# HandschuhSimplified.net
KiCad netlist of a schematic drawn in EAGLE
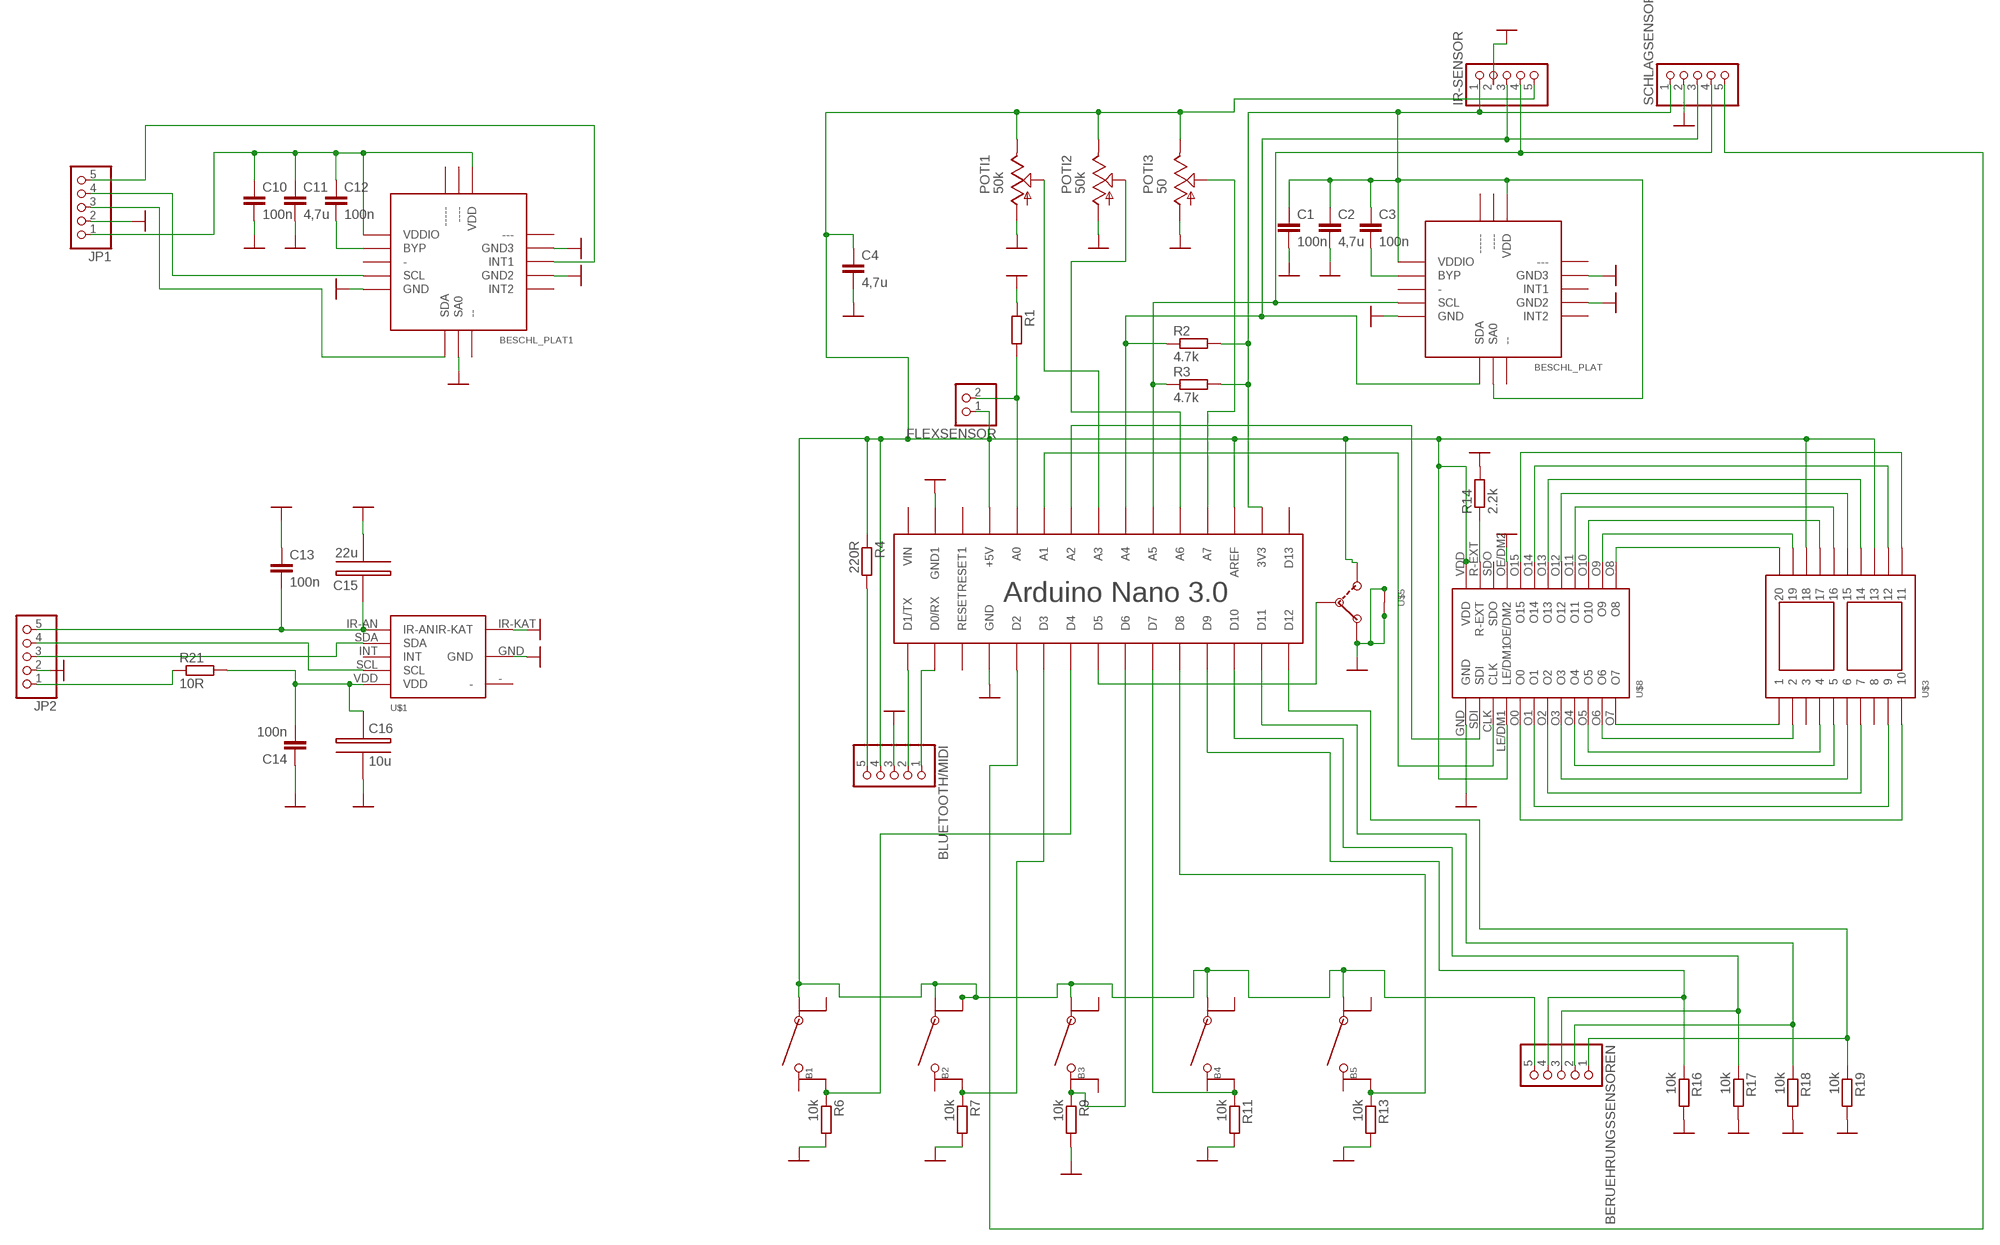
[diagram p0: schematic, sheet 1]

(export (version "E")
  (design (tool "Eeschema 10.0.6"))
  (components
    (comp (ref "B1")
      (value "BUTTON")
      (footprint "eagle-import:BUTTON")
      (libsource (lib "eagle-import") (part "BUTTON"))
    )
    (comp (ref "B2")
      (value "BUTTON")
      (footprint "eagle-import:BUTTON")
      (libsource (lib "eagle-import") (part "BUTTON"))
    )
    (comp (ref "B3")
      (value "BUTTON")
      (footprint "eagle-import:BUTTON")
      (libsource (lib "eagle-import") (part "BUTTON"))
    )
    (comp (ref "B4")
      (value "BUTTON")
      (footprint "eagle-import:BUTTON")
      (libsource (lib "eagle-import") (part "BUTTON"))
    )
    (comp (ref "B5")
      (value "BUTTON")
      (footprint "eagle-import:BUTTON")
      (libsource (lib "eagle-import") (part "BUTTON"))
    )
    (comp (ref "BERUEHRUNGSSENSOREN")
      (value "PINHD-1X5/90")
      (footprint "eagle-import:1X05_90")
      (libsource (lib "eagle-import") (part "PINHD-1X5/90"))
    )
    (comp (ref "BESCHL_PLAT")
      (value "BESCHLEUNIGSUNGSSENSOR")
      (footprint "eagle-import:BESCHLEUNIGUNGSSENSOR")
      (libsource (lib "eagle-import") (part "BESCHLEUNIGSUNGSSENSOR"))
    )
    (comp (ref "BESCHL_PLAT1")
      (value "BESCHLEUNIGSUNGSSENSOR")
      (footprint "eagle-import:BESCHLEUNIGUNGSSENSOR")
      (libsource (lib "eagle-import") (part "BESCHLEUNIGSUNGSSENSOR"))
    )
    (comp (ref "BLUETOOTH/MIDI")
      (value "PINHD-1X5/90")
      (footprint "eagle-import:1X05_90")
      (libsource (lib "eagle-import") (part "PINHD-1X5/90"))
    )
    (comp (ref "C1")
      (value "100n")
      (footprint "eagle-import:C0805")
      (libsource (lib "eagle-import") (part "C-EUC0805"))
    )
    (comp (ref "C2")
      (value "4,7u")
      (footprint "eagle-import:C0805")
      (libsource (lib "eagle-import") (part "C-EUC0805"))
    )
    (comp (ref "C3")
      (value "100n")
      (footprint "eagle-import:C0805")
      (libsource (lib "eagle-import") (part "C-EUC0805"))
    )
    (comp (ref "C4")
      (value "4,7u")
      (footprint "eagle-import:C0805")
      (libsource (lib "eagle-import") (part "C-EUC0805"))
    )
    (comp (ref "C10")
      (value "100n")
      (footprint "eagle-import:C0805")
      (libsource (lib "eagle-import") (part "C-EUC0805"))
    )
    (comp (ref "C11")
      (value "4,7u")
      (footprint "eagle-import:C0805")
      (libsource (lib "eagle-import") (part "C-EUC0805"))
    )
    (comp (ref "C12")
      (value "100n")
      (footprint "eagle-import:C0805")
      (libsource (lib "eagle-import") (part "C-EUC0805"))
    )
    (comp (ref "C13")
      (value "100n")
      (footprint "eagle-import:C0805")
      (libsource (lib "eagle-import") (part "C-EUC0805"))
    )
    (comp (ref "C14")
      (value "100n")
      (footprint "eagle-import:C0805")
      (libsource (lib "eagle-import") (part "C-EUC0805"))
    )
    (comp (ref "C15")
      (value "22u")
      (footprint "eagle-import:22U-KONDENSATOR")
      (libsource (lib "eagle-import") (part "22U-KONDENSATOR"))
    )
    (comp (ref "C16")
      (value "10u")
      (footprint "eagle-import:22U-KONDENSATOR")
      (libsource (lib "eagle-import") (part "22U-KONDENSATOR"))
    )
    (comp (ref "FLEXSENSOR")
      (value "PINHD-1X2/90")
      (footprint "eagle-import:1X02_90")
      (libsource (lib "eagle-import") (part "PINHD-1X2/90"))
    )
    (comp (ref "IR-SENSOR")
      (value "PINHD-1X5/90")
      (footprint "eagle-import:1X05_90")
      (libsource (lib "eagle-import") (part "PINHD-1X5/90"))
    )
    (comp (ref "JP1")
      (value "PINHD-1X5/90")
      (footprint "eagle-import:1X05_90")
      (libsource (lib "eagle-import") (part "PINHD-1X5/90"))
    )
    (comp (ref "JP2")
      (value "PINHD-1X5/90")
      (footprint "eagle-import:1X05_90")
      (libsource (lib "eagle-import") (part "PINHD-1X5/90"))
    )
    (comp (ref "POTI1")
      (value "50k")
      (footprint "eagle-import:POTI")
      (libsource (lib "eagle-import") (part "POTI"))
    )
    (comp (ref "POTI2")
      (value "50k")
      (footprint "eagle-import:POTI")
      (libsource (lib "eagle-import") (part "POTI"))
    )
    (comp (ref "POTI3")
      (value "50")
      (footprint "eagle-import:POTI")
      (libsource (lib "eagle-import") (part "POTI"))
    )
    (comp (ref "R1")
      (value "R-EU_M0805")
      (footprint "eagle-import:M0805")
      (libsource (lib "eagle-import") (part "R-EU_M0805"))
    )
    (comp (ref "R2")
      (value "4.7k")
      (footprint "eagle-import:M0805")
      (libsource (lib "eagle-import") (part "R-EU_M0805"))
    )
    (comp (ref "R3")
      (value "4.7k")
      (footprint "eagle-import:M0805")
      (libsource (lib "eagle-import") (part "R-EU_M0805"))
    )
    (comp (ref "R4")
      (value "220R")
      (footprint "eagle-import:M0805")
      (libsource (lib "eagle-import") (part "R-EU_M0805"))
    )
    (comp (ref "R6")
      (value "10k")
      (footprint "eagle-import:M0805")
      (libsource (lib "eagle-import") (part "R-EU_M0805"))
    )
    (comp (ref "R7")
      (value "10k")
      (footprint "eagle-import:M0805")
      (libsource (lib "eagle-import") (part "R-EU_M0805"))
    )
    (comp (ref "R9")
      (value "10k")
      (footprint "eagle-import:M0805")
      (libsource (lib "eagle-import") (part "R-EU_M0805"))
    )
    (comp (ref "R11")
      (value "10k")
      (footprint "eagle-import:M0805")
      (libsource (lib "eagle-import") (part "R-EU_M0805"))
    )
    (comp (ref "R13")
      (value "10k")
      (footprint "eagle-import:M0805")
      (libsource (lib "eagle-import") (part "R-EU_M0805"))
    )
    (comp (ref "R14")
      (value "2.2k")
      (footprint "eagle-import:M0805")
      (libsource (lib "eagle-import") (part "R-EU_M0805"))
    )
    (comp (ref "R16")
      (value "10k")
      (footprint "eagle-import:M0805")
      (libsource (lib "eagle-import") (part "R-EU_M0805"))
    )
    (comp (ref "R17")
      (value "10k")
      (footprint "eagle-import:M0805")
      (libsource (lib "eagle-import") (part "R-EU_M0805"))
    )
    (comp (ref "R18")
      (value "10k")
      (footprint "eagle-import:M0805")
      (libsource (lib "eagle-import") (part "R-EU_M0805"))
    )
    (comp (ref "R19")
      (value "10k")
      (footprint "eagle-import:M0805")
      (libsource (lib "eagle-import") (part "R-EU_M0805"))
    )
    (comp (ref "R21")
      (value "10R")
      (footprint "eagle-import:M0805")
      (libsource (lib "eagle-import") (part "R-EU_M0805"))
    )
    (comp (ref "SCHLAGSENSOR")
      (value "PINHD-1X5/90")
      (footprint "eagle-import:1X05_90")
      (libsource (lib "eagle-import") (part "PINHD-1X5/90"))
    )
    (comp (ref "U$1")
      (value "IR-SENSOR")
      (footprint "eagle-import:IR-SENSOR")
      (libsource (lib "eagle-import") (part "IR-SENSOR"))
    )
    (comp (ref "U$2")
      (value "ARDUINONANO")
      (footprint "eagle-import:PDIP-32")
      (libsource (lib "eagle-import") (part "ARDUINONANO"))
    )
    (comp (ref "U$3")
      (value "7-SEGMENT")
      (footprint "eagle-import:7-SEGMENT")
      (libsource (lib "eagle-import") (part "7-SEGMENT"))
    )
    (comp (ref "U$5")
      (value "SCHALTER")
      (footprint "eagle-import:SCHALTER")
      (libsource (lib "eagle-import") (part "SCHALTER"))
    )
    (comp (ref "U$8")
      (value "7-SEGMENT-TREIBER")
      (footprint "eagle-import:7-SEGMENT-TREIBER")
      (libsource (lib "eagle-import") (part "7-SEGMENT-TREIBER"))
    )
  )
  (nets
    (net (code "1") (name "Net-(B1-Pad2)") (class "Default")
      (node (ref "B1") (pin "2") (pinfunction "2_2") (pintype "bidirectional"))
      (node (ref "R6") (pin "1") (pinfunction "1_1") (pintype "passive"))
      (node (ref "U$2") (pin "D4") (pinfunction "D4_D4") (pintype "bidirectional"))
    )
    (net (code "2") (name "Net-(B1-Pad3)") (class "Default")
      (node (ref "B1") (pin "3") (pinfunction "3_3") (pintype "bidirectional"))
      (node (ref "B2") (pin "3") (pinfunction "3_3") (pintype "bidirectional"))
      (node (ref "B2") (pin "4") (pinfunction "4_4") (pintype "bidirectional"))
      (node (ref "B3") (pin "3") (pinfunction "3_3") (pintype "bidirectional"))
      (node (ref "B4") (pin "3") (pinfunction "3_3") (pintype "bidirectional"))
      (node (ref "B5") (pin "3") (pinfunction "3_3") (pintype "bidirectional"))
      (node (ref "BERUEHRUNGSSENSOREN") (pin "5") (pinfunction "5_5") (pintype "passive"))
      (node (ref "BLUETOOTH/MIDI") (pin "4") (pinfunction "4_4") (pintype "passive"))
      (node (ref "C4") (pin "1") (pinfunction "1_1") (pintype "passive"))
      (node (ref "FLEXSENSOR") (pin "1") (pinfunction "1_1") (pintype "passive"))
      (node (ref "IR-SENSOR") (pin "5") (pinfunction "5_5") (pintype "passive"))
      (node (ref "POTI1") (pin "VCC") (pinfunction "VCC_VCC") (pintype "passive"))
      (node (ref "POTI2") (pin "VCC") (pinfunction "VCC_VCC") (pintype "passive"))
      (node (ref "POTI3") (pin "VCC") (pinfunction "VCC_VCC") (pintype "passive"))
      (node (ref "R4") (pin "1") (pinfunction "1_1") (pintype "passive"))
      (node (ref "U$2") (pin "+5V") (pinfunction "+5V_+5V") (pintype "bidirectional"))
      (node (ref "U$2") (pin "AREF") (pinfunction "AREF_AREF") (pintype "bidirectional"))
      (node (ref "U$3") (pin "13") (pinfunction "13_13") (pintype "bidirectional"))
      (node (ref "U$3") (pin "18") (pinfunction "18_18") (pintype "bidirectional"))
      (node (ref "U$5") (pin "3") (pinfunction "3_3") (pintype "bidirectional"))
      (node (ref "U$8") (pin "LE/DM1") (pinfunction "LE/DM1_LE/DM1") (pintype "bidirectional"))
      (node (ref "U$8") (pin "VDD") (pinfunction "VDD_VDD") (pintype "bidirectional"))
    )
    (net (code "3") (name "Net-(B2-Pad2)") (class "Default")
      (node (ref "B2") (pin "2") (pinfunction "2_2") (pintype "bidirectional"))
      (node (ref "R7") (pin "1") (pinfunction "1_1") (pintype "passive"))
      (node (ref "U$2") (pin "D3") (pinfunction "D3_D3") (pintype "bidirectional"))
    )
    (net (code "4") (name "Net-(B3-Pad1)") (class "Default")
      (node (ref "B3") (pin "1") (pinfunction "1_1") (pintype "bidirectional"))
      (node (ref "R9") (pin "1") (pinfunction "1_1") (pintype "passive"))
      (node (ref "U$2") (pin "D6") (pinfunction "D6_D6") (pintype "bidirectional"))
    )
    (net (code "5") (name "Net-(B4-Pad2)") (class "Default")
      (node (ref "B4") (pin "2") (pinfunction "2_2") (pintype "bidirectional"))
      (node (ref "R11") (pin "1") (pinfunction "1_1") (pintype "passive"))
      (node (ref "U$2") (pin "D7") (pinfunction "D7_D7") (pintype "bidirectional"))
    )
    (net (code "6") (name "Net-(B5-Pad2)") (class "Default")
      (node (ref "B5") (pin "2") (pinfunction "2_2") (pintype "bidirectional"))
      (node (ref "R13") (pin "1") (pinfunction "1_1") (pintype "passive"))
      (node (ref "U$2") (pin "D8") (pinfunction "D8_D8") (pintype "bidirectional"))
    )
    (net (code "7") (name "Net-(BERUEHRUNGSSENSOREN-Pad1)") (class "Default")
      (node (ref "BERUEHRUNGSSENSOREN") (pin "1") (pinfunction "1_1") (pintype "passive"))
      (node (ref "R19") (pin "1") (pinfunction "1_1") (pintype "passive"))
      (node (ref "U$2") (pin "D12") (pinfunction "D12_D12") (pintype "bidirectional"))
    )
    (net (code "8") (name "Net-(BERUEHRUNGSSENSOREN-Pad2)") (class "Default")
      (node (ref "BERUEHRUNGSSENSOREN") (pin "2") (pinfunction "2_2") (pintype "passive"))
      (node (ref "R18") (pin "1") (pinfunction "1_1") (pintype "passive"))
      (node (ref "U$2") (pin "D11") (pinfunction "D11_D11") (pintype "bidirectional"))
    )
    (net (code "9") (name "Net-(BERUEHRUNGSSENSOREN-Pad3)") (class "Default")
      (node (ref "BERUEHRUNGSSENSOREN") (pin "3") (pinfunction "3_3") (pintype "passive"))
      (node (ref "R17") (pin "1") (pinfunction "1_1") (pintype "passive"))
      (node (ref "U$2") (pin "D10") (pinfunction "D10_D10") (pintype "bidirectional"))
    )
    (net (code "10") (name "Net-(BERUEHRUNGSSENSOREN-Pad4)") (class "Default")
      (node (ref "BERUEHRUNGSSENSOREN") (pin "4") (pinfunction "4_4") (pintype "passive"))
      (node (ref "R16") (pin "1") (pinfunction "1_1") (pintype "passive"))
      (node (ref "U$2") (pin "D9") (pinfunction "D9_D9") (pintype "bidirectional"))
    )
    (net (code "11") (name "Net-(BESCHL_PLAT-PadBYP)") (class "Default")
      (node (ref "BESCHL_PLAT") (pin "BYP") (pinfunction "BYP_BYP") (pintype "bidirectional"))
      (node (ref "C3") (pin "2") (pinfunction "2_2") (pintype "passive"))
    )
    (net (code "12") (name "Net-(BESCHL_PLAT-PadSA0)") (class "Default")
      (node (ref "BESCHL_PLAT") (pin "SA0") (pinfunction "SA0_SA0") (pintype "bidirectional"))
      (node (ref "BESCHL_PLAT") (pin "VDD") (pinfunction "VDD_VDD") (pintype "bidirectional"))
      (node (ref "BESCHL_PLAT") (pin "VDDIO") (pinfunction "VDDIO_VDDIO") (pintype "bidirectional"))
      (node (ref "C1") (pin "1") (pinfunction "1_1") (pintype "passive"))
      (node (ref "C2") (pin "1") (pinfunction "1_1") (pintype "passive"))
      (node (ref "C3") (pin "1") (pinfunction "1_1") (pintype "passive"))
      (node (ref "IR-SENSOR") (pin "1") (pinfunction "1_1") (pintype "passive"))
      (node (ref "R2") (pin "2") (pinfunction "2_2") (pintype "passive"))
      (node (ref "R3") (pin "2") (pinfunction "2_2") (pintype "passive"))
      (node (ref "SCHLAGSENSOR") (pin "1") (pinfunction "1_1") (pintype "passive"))
      (node (ref "U$2") (pin "3V3") (pinfunction "3V3_3V3") (pintype "bidirectional"))
    )
    (net (code "13") (name "Net-(BESCHL_PLAT-PadSCL)") (class "Default")
      (node (ref "BESCHL_PLAT") (pin "SCL") (pinfunction "SCL_SCL") (pintype "bidirectional"))
      (node (ref "IR-SENSOR") (pin "4") (pinfunction "4_4") (pintype "passive"))
      (node (ref "R3") (pin "1") (pinfunction "1_1") (pintype "passive"))
      (node (ref "SCHLAGSENSOR") (pin "4") (pinfunction "4_4") (pintype "passive"))
      (node (ref "U$2") (pin "A5") (pinfunction "A5_A5") (pintype "bidirectional"))
    )
    (net (code "14") (name "Net-(BESCHL_PLAT-PadSDA)") (class "Default")
      (node (ref "BESCHL_PLAT") (pin "SDA") (pinfunction "SDA_SDA") (pintype "bidirectional"))
      (node (ref "IR-SENSOR") (pin "3") (pinfunction "3_3") (pintype "passive"))
      (node (ref "R2") (pin "1") (pinfunction "1_1") (pintype "passive"))
      (node (ref "SCHLAGSENSOR") (pin "3") (pinfunction "3_3") (pintype "passive"))
      (node (ref "U$2") (pin "A4") (pinfunction "A4_A4") (pintype "bidirectional"))
    )
    (net (code "15") (name "Net-(BESCHL_PLAT1-PadBYP)") (class "Default")
      (node (ref "BESCHL_PLAT1") (pin "BYP") (pinfunction "BYP_BYP") (pintype "bidirectional"))
      (node (ref "C12") (pin "2") (pinfunction "2_2") (pintype "passive"))
    )
    (net (code "16") (name "Net-(BESCHL_PLAT1-PadINT1)") (class "Default")
      (node (ref "BESCHL_PLAT1") (pin "INT1") (pinfunction "INT1_INT1") (pintype "bidirectional"))
      (node (ref "JP1") (pin "5") (pinfunction "5_5") (pintype "passive"))
    )
    (net (code "17") (name "Net-(BESCHL_PLAT1-PadSCL)") (class "Default")
      (node (ref "BESCHL_PLAT1") (pin "SCL") (pinfunction "SCL_SCL") (pintype "bidirectional"))
      (node (ref "JP1") (pin "4") (pinfunction "4_4") (pintype "passive"))
    )
    (net (code "18") (name "Net-(BESCHL_PLAT1-PadSDA)") (class "Default")
      (node (ref "BESCHL_PLAT1") (pin "SDA") (pinfunction "SDA_SDA") (pintype "bidirectional"))
      (node (ref "JP1") (pin "3") (pinfunction "3_3") (pintype "passive"))
    )
    (net (code "19") (name "Net-(BESCHL_PLAT1-PadVDD)") (class "Default")
      (node (ref "BESCHL_PLAT1") (pin "VDD") (pinfunction "VDD_VDD") (pintype "bidirectional"))
      (node (ref "BESCHL_PLAT1") (pin "VDDIO") (pinfunction "VDDIO_VDDIO") (pintype "bidirectional"))
      (node (ref "C10") (pin "1") (pinfunction "1_1") (pintype "passive"))
      (node (ref "C11") (pin "1") (pinfunction "1_1") (pintype "passive"))
      (node (ref "C12") (pin "1") (pinfunction "1_1") (pintype "passive"))
      (node (ref "JP1") (pin "1") (pinfunction "1_1") (pintype "passive"))
    )
    (net (code "20") (name "Net-(BLUETOOTH/MIDI-Pad1)") (class "Default")
      (node (ref "BLUETOOTH/MIDI") (pin "1") (pinfunction "1_1") (pintype "passive"))
      (node (ref "U$2") (pin "D0/RX") (pinfunction "D0/RX_D0/RX") (pintype "bidirectional"))
    )
    (net (code "21") (name "Net-(BLUETOOTH/MIDI-Pad2)") (class "Default")
      (node (ref "BLUETOOTH/MIDI") (pin "2") (pinfunction "2_2") (pintype "passive"))
      (node (ref "U$2") (pin "D1/TX") (pinfunction "D1/TX_D1/TX") (pintype "bidirectional"))
    )
    (net (code "22") (name "Net-(BLUETOOTH/MIDI-Pad5)") (class "Default")
      (node (ref "BLUETOOTH/MIDI") (pin "5") (pinfunction "5_5") (pintype "passive"))
      (node (ref "R4") (pin "2") (pinfunction "2_2") (pintype "passive"))
    )
    (net (code "23") (name "Net-(C13-Pad2)") (class "Default")
      (node (ref "C13") (pin "2") (pinfunction "2_2") (pintype "passive"))
      (node (ref "C15") (pin "+") (pinfunction "+_+") (pintype "bidirectional"))
      (node (ref "JP2") (pin "5") (pinfunction "5_5") (pintype "passive"))
      (node (ref "U$1") (pin "IR-AN") (pinfunction "IR-AN_IR-AN") (pintype "bidirectional"))
    )
    (net (code "24") (name "Net-(C14-Pad2)") (class "Default")
      (node (ref "C14") (pin "2") (pinfunction "2_2") (pintype "passive"))
      (node (ref "C16") (pin "+") (pinfunction "+_+") (pintype "bidirectional"))
      (node (ref "R21") (pin "2") (pinfunction "2_2") (pintype "passive"))
      (node (ref "U$1") (pin "VDD") (pinfunction "VDD_VDD") (pintype "bidirectional"))
    )
    (net (code "25") (name "Net-(FLEXSENSOR-Pad2)") (class "Default")
      (node (ref "FLEXSENSOR") (pin "2") (pinfunction "2_2") (pintype "passive"))
      (node (ref "R1") (pin "2") (pinfunction "2_2") (pintype "passive"))
      (node (ref "U$2") (pin "A0") (pinfunction "A0_A0") (pintype "bidirectional"))
    )
    (net (code "26") (name "Net-(JP2-Pad1)") (class "Default")
      (node (ref "JP2") (pin "1") (pinfunction "1_1") (pintype "passive"))
      (node (ref "R21") (pin "1") (pinfunction "1_1") (pintype "passive"))
    )
    (net (code "27") (name "Net-(JP2-Pad3)") (class "Default")
      (node (ref "JP2") (pin "3") (pinfunction "3_3") (pintype "passive"))
      (node (ref "U$1") (pin "SDA") (pinfunction "SDA_SDA") (pintype "bidirectional"))
    )
    (net (code "28") (name "Net-(JP2-Pad4)") (class "Default")
      (node (ref "JP2") (pin "4") (pinfunction "4_4") (pintype "passive"))
      (node (ref "U$1") (pin "SCL") (pinfunction "SCL_SCL") (pintype "bidirectional"))
    )
    (net (code "29") (name "Net-(POTI1-PadVALUE)") (class "Default")
      (node (ref "POTI1") (pin "VALUE") (pinfunction "VALUE_VALUE") (pintype "passive"))
      (node (ref "U$2") (pin "A3") (pinfunction "A3_A3") (pintype "bidirectional"))
    )
    (net (code "30") (name "Net-(POTI2-PadVALUE)") (class "Default")
      (node (ref "POTI2") (pin "VALUE") (pinfunction "VALUE_VALUE") (pintype "passive"))
      (node (ref "U$2") (pin "A6") (pinfunction "A6_A6") (pintype "bidirectional"))
    )
    (net (code "31") (name "Net-(POTI3-PadVALUE)") (class "Default")
      (node (ref "POTI3") (pin "VALUE") (pinfunction "VALUE_VALUE") (pintype "passive"))
      (node (ref "U$2") (pin "A7") (pinfunction "A7_A7") (pintype "bidirectional"))
    )
    (net (code "32") (name "Net-(R14-Pad1)") (class "Default")
      (node (ref "R14") (pin "1") (pinfunction "1_1") (pintype "passive"))
      (node (ref "U$8") (pin "R-EXT") (pinfunction "R-EXT_R-EXT") (pintype "bidirectional"))
    )
    (net (code "33") (name "Net-(SCHLAGSENSOR-Pad5)") (class "Default")
      (node (ref "SCHLAGSENSOR") (pin "5") (pinfunction "5_5") (pintype "passive"))
      (node (ref "U$2") (pin "D2") (pinfunction "D2_D2") (pintype "bidirectional"))
    )
    (net (code "34") (name "Net-(U$2-PadA1)") (class "Default")
      (node (ref "U$2") (pin "A1") (pinfunction "A1_A1") (pintype "bidirectional"))
      (node (ref "U$8") (pin "CLK") (pinfunction "CLK_CLK") (pintype "bidirectional"))
    )
    (net (code "35") (name "Net-(U$2-PadA2)") (class "Default")
      (node (ref "U$2") (pin "A2") (pinfunction "A2_A2") (pintype "bidirectional"))
      (node (ref "U$8") (pin "SDI") (pinfunction "SDI_SDI") (pintype "bidirectional"))
    )
    (net (code "36") (name "Net-(U$2-PadD5)") (class "Default")
      (node (ref "U$2") (pin "D5") (pinfunction "D5_D5") (pintype "bidirectional"))
      (node (ref "U$5") (pin "2") (pinfunction "2_2") (pintype "bidirectional"))
    )
    (net (code "37") (name "Net-(U$3-Pad1)") (class "Default")
      (node (ref "U$3") (pin "1") (pinfunction "1_1") (pintype "bidirectional"))
      (node (ref "U$8") (pin "O7") (pinfunction "O7_O7") (pintype "bidirectional"))
    )
    (net (code "38") (name "Net-(U$3-Pad2)") (class "Default")
      (node (ref "U$3") (pin "2") (pinfunction "2_2") (pintype "bidirectional"))
      (node (ref "U$8") (pin "O6") (pinfunction "O6_O6") (pintype "bidirectional"))
    )
    (net (code "39") (name "Net-(U$3-Pad4)") (class "Default")
      (node (ref "U$3") (pin "4") (pinfunction "4_4") (pintype "bidirectional"))
      (node (ref "U$8") (pin "O5") (pinfunction "O5_O5") (pintype "bidirectional"))
    )
    (net (code "40") (name "Net-(U$3-Pad5)") (class "Default")
      (node (ref "U$3") (pin "5") (pinfunction "5_5") (pintype "bidirectional"))
      (node (ref "U$8") (pin "O4") (pinfunction "O4_O4") (pintype "bidirectional"))
    )
    (net (code "41") (name "Net-(U$3-Pad6)") (class "Default")
      (node (ref "U$3") (pin "6") (pinfunction "6_6") (pintype "bidirectional"))
      (node (ref "U$8") (pin "O3") (pinfunction "O3_O3") (pintype "bidirectional"))
    )
    (net (code "42") (name "Net-(U$3-Pad7)") (class "Default")
      (node (ref "U$3") (pin "7") (pinfunction "7_7") (pintype "bidirectional"))
      (node (ref "U$8") (pin "O2") (pinfunction "O2_O2") (pintype "bidirectional"))
    )
    (net (code "43") (name "Net-(U$3-Pad9)") (class "Default")
      (node (ref "U$3") (pin "9") (pinfunction "9_9") (pintype "bidirectional"))
      (node (ref "U$8") (pin "O1") (pinfunction "O1_O1") (pintype "bidirectional"))
    )
    (net (code "44") (name "Net-(U$3-Pad10)") (class "Default")
      (node (ref "U$3") (pin "10") (pinfunction "10_10") (pintype "bidirectional"))
      (node (ref "U$8") (pin "O0") (pinfunction "O0_O0") (pintype "bidirectional"))
    )
    (net (code "45") (name "Net-(U$3-Pad11)") (class "Default")
      (node (ref "U$3") (pin "11") (pinfunction "11_11") (pintype "bidirectional"))
      (node (ref "U$8") (pin "O15") (pinfunction "O15_O15") (pintype "bidirectional"))
    )
    (net (code "46") (name "Net-(U$3-Pad12)") (class "Default")
      (node (ref "U$3") (pin "12") (pinfunction "12_12") (pintype "bidirectional"))
      (node (ref "U$8") (pin "O14") (pinfunction "O14_O14") (pintype "bidirectional"))
    )
    (net (code "47") (name "Net-(U$3-Pad14)") (class "Default")
      (node (ref "U$3") (pin "14") (pinfunction "14_14") (pintype "bidirectional"))
      (node (ref "U$8") (pin "O13") (pinfunction "O13_O13") (pintype "bidirectional"))
    )
    (net (code "48") (name "Net-(U$3-Pad15)") (class "Default")
      (node (ref "U$3") (pin "15") (pinfunction "15_15") (pintype "bidirectional"))
      (node (ref "U$8") (pin "O12") (pinfunction "O12_O12") (pintype "bidirectional"))
    )
    (net (code "49") (name "Net-(U$3-Pad16)") (class "Default")
      (node (ref "U$3") (pin "16") (pinfunction "16_16") (pintype "bidirectional"))
      (node (ref "U$8") (pin "O11") (pinfunction "O11_O11") (pintype "bidirectional"))
    )
    (net (code "50") (name "Net-(U$3-Pad17)") (class "Default")
      (node (ref "U$3") (pin "17") (pinfunction "17_17") (pintype "bidirectional"))
      (node (ref "U$8") (pin "O10") (pinfunction "O10_O10") (pintype "bidirectional"))
    )
    (net (code "51") (name "Net-(U$3-Pad19)") (class "Default")
      (node (ref "U$3") (pin "19") (pinfunction "19_19") (pintype "bidirectional"))
      (node (ref "U$8") (pin "O9") (pinfunction "O9_O9") (pintype "bidirectional"))
    )
    (net (code "52") (name "Net-(U$3-Pad20)") (class "Default")
      (node (ref "U$3") (pin "20") (pinfunction "20_20") (pintype "bidirectional"))
      (node (ref "U$8") (pin "O8") (pinfunction "O8_O8") (pintype "bidirectional"))
    )
    (net (code "53") (name "POWER_SUPPLY1_GND") (class "Default")
      (node (ref "BESCHL_PLAT") (pin "GND") (pinfunction "GND_GND") (pintype "bidirectional"))
      (node (ref "BESCHL_PLAT") (pin "GND2") (pinfunction "GND2_GND2") (pintype "bidirectional"))
      (node (ref "BESCHL_PLAT") (pin "GND3") (pinfunction "GND3_GND3") (pintype "bidirectional"))
      (node (ref "BESCHL_PLAT1") (pin "GND") (pinfunction "GND_GND") (pintype "bidirectional"))
      (node (ref "BESCHL_PLAT1") (pin "GND2") (pinfunction "GND2_GND2") (pintype "bidirectional"))
      (node (ref "BESCHL_PLAT1") (pin "GND3") (pinfunction "GND3_GND3") (pintype "bidirectional"))
      (node (ref "BESCHL_PLAT1") (pin "SA0") (pinfunction "SA0_SA0") (pintype "bidirectional"))
      (node (ref "BLUETOOTH/MIDI") (pin "3") (pinfunction "3_3") (pintype "passive"))
      (node (ref "C1") (pin "2") (pinfunction "2_2") (pintype "passive"))
      (node (ref "C10") (pin "2") (pinfunction "2_2") (pintype "passive"))
      (node (ref "C11") (pin "2") (pinfunction "2_2") (pintype "passive"))
      (node (ref "C13") (pin "1") (pinfunction "1_1") (pintype "passive"))
      (node (ref "C14") (pin "1") (pinfunction "1_1") (pintype "passive"))
      (node (ref "C15") (pin "-") (pinfunction "-_-") (pintype "bidirectional"))
      (node (ref "C16") (pin "-") (pinfunction "-_-") (pintype "bidirectional"))
      (node (ref "C2") (pin "2") (pinfunction "2_2") (pintype "passive"))
      (node (ref "C4") (pin "2") (pinfunction "2_2") (pintype "passive"))
      (node (ref "IR-SENSOR") (pin "2") (pinfunction "2_2") (pintype "passive"))
      (node (ref "JP1") (pin "2") (pinfunction "2_2") (pintype "passive"))
      (node (ref "JP2") (pin "2") (pinfunction "2_2") (pintype "passive"))
      (node (ref "POTI1") (pin "GND") (pinfunction "GND_GND") (pintype "passive"))
      (node (ref "POTI2") (pin "GND") (pinfunction "GND_GND") (pintype "passive"))
      (node (ref "POTI3") (pin "GND") (pinfunction "GND_GND") (pintype "passive"))
      (node (ref "R1") (pin "1") (pinfunction "1_1") (pintype "passive"))
      (node (ref "R11") (pin "2") (pinfunction "2_2") (pintype "passive"))
      (node (ref "R13") (pin "2") (pinfunction "2_2") (pintype "passive"))
      (node (ref "R14") (pin "2") (pinfunction "2_2") (pintype "passive"))
      (node (ref "R16") (pin "2") (pinfunction "2_2") (pintype "passive"))
      (node (ref "R17") (pin "2") (pinfunction "2_2") (pintype "passive"))
      (node (ref "R18") (pin "2") (pinfunction "2_2") (pintype "passive"))
      (node (ref "R19") (pin "2") (pinfunction "2_2") (pintype "passive"))
      (node (ref "R6") (pin "2") (pinfunction "2_2") (pintype "passive"))
      (node (ref "R7") (pin "2") (pinfunction "2_2") (pintype "passive"))
      (node (ref "R9") (pin "2") (pinfunction "2_2") (pintype "passive"))
      (node (ref "SCHLAGSENSOR") (pin "2") (pinfunction "2_2") (pintype "passive"))
      (node (ref "U$1") (pin "GND") (pinfunction "GND_GND") (pintype "bidirectional"))
      (node (ref "U$1") (pin "IR-KAT") (pinfunction "IR-KAT_IR-KAT") (pintype "bidirectional"))
      (node (ref "U$2") (pin "GND") (pinfunction "GND_GND") (pintype "bidirectional"))
      (node (ref "U$2") (pin "GND1") (pinfunction "GND1_GND1") (pintype "bidirectional"))
      (node (ref "U$5") (pin "1") (pinfunction "1_1") (pintype "bidirectional"))
      (node (ref "U$5") (pin "4") (pinfunction "4_4") (pintype "bidirectional"))
      (node (ref "U$5") (pin "5") (pinfunction "5_5") (pintype "bidirectional"))
      (node (ref "U$8") (pin "GND") (pinfunction "GND_GND") (pintype "bidirectional"))
      (node (ref "U$8") (pin "OE/DM2") (pinfunction "OE/DM2_OE/DM2") (pintype "bidirectional"))
    )
    (net (code "54") (name "unconnected-(B1-Pad1)") (class "Default")
      (node (ref "B1") (pin "1") (pinfunction "1_1") (pintype "bidirectional"))
    )
    (net (code "55") (name "unconnected-(B1-Pad4)") (class "Default")
      (node (ref "B1") (pin "4") (pinfunction "4_4") (pintype "bidirectional"))
    )
    (net (code "56") (name "unconnected-(B2-Pad1)") (class "Default")
      (node (ref "B2") (pin "1") (pinfunction "1_1") (pintype "bidirectional"))
    )
    (net (code "57") (name "unconnected-(B3-Pad2)") (class "Default")
      (node (ref "B3") (pin "2") (pinfunction "2_2") (pintype "bidirectional"))
    )
    (net (code "58") (name "unconnected-(B3-Pad4)") (class "Default")
      (node (ref "B3") (pin "4") (pinfunction "4_4") (pintype "bidirectional"))
    )
    (net (code "59") (name "unconnected-(B4-Pad1)") (class "Default")
      (node (ref "B4") (pin "1") (pinfunction "1_1") (pintype "bidirectional"))
    )
    (net (code "60") (name "unconnected-(B4-Pad4)") (class "Default")
      (node (ref "B4") (pin "4") (pinfunction "4_4") (pintype "bidirectional"))
    )
    (net (code "61") (name "unconnected-(B5-Pad1)") (class "Default")
      (node (ref "B5") (pin "1") (pinfunction "1_1") (pintype "bidirectional"))
    )
    (net (code "62") (name "unconnected-(B5-Pad4)") (class "Default")
      (node (ref "B5") (pin "4") (pinfunction "4_4") (pintype "bidirectional"))
    )
    (net (code "63") (name "unconnected-(BESCHL_PLAT-Pad-)") (class "Default")
      (node (ref "BESCHL_PLAT") (pin "-") (pinfunction "-_-") (pintype "bidirectional"))
    )
    (net (code "64") (name "unconnected-(BESCHL_PLAT-Pad--)") (class "Default")
      (node (ref "BESCHL_PLAT") (pin "--") (pinfunction "--_--") (pintype "bidirectional"))
    )
    (net (code "65") (name "unconnected-(BESCHL_PLAT-Pad---)") (class "Default")
      (node (ref "BESCHL_PLAT") (pin "---") (pinfunction "---_---") (pintype "bidirectional"))
    )
    (net (code "66") (name "unconnected-(BESCHL_PLAT-Pad----)") (class "Default")
      (node (ref "BESCHL_PLAT") (pin "----") (pinfunction "----_----") (pintype "bidirectional"))
    )
    (net (code "67") (name "unconnected-(BESCHL_PLAT-Pad-----)") (class "Default")
      (node (ref "BESCHL_PLAT") (pin "-----") (pinfunction "-----_-----") (pintype "bidirectional"))
    )
    (net (code "68") (name "unconnected-(BESCHL_PLAT-PadINT1)") (class "Default")
      (node (ref "BESCHL_PLAT") (pin "INT1") (pinfunction "INT1_INT1") (pintype "bidirectional"))
    )
    (net (code "69") (name "unconnected-(BESCHL_PLAT-PadINT2)") (class "Default")
      (node (ref "BESCHL_PLAT") (pin "INT2") (pinfunction "INT2_INT2") (pintype "bidirectional"))
    )
    (net (code "70") (name "unconnected-(BESCHL_PLAT1-Pad-)") (class "Default")
      (node (ref "BESCHL_PLAT1") (pin "-") (pinfunction "-_-") (pintype "bidirectional"))
    )
    (net (code "71") (name "unconnected-(BESCHL_PLAT1-Pad--)") (class "Default")
      (node (ref "BESCHL_PLAT1") (pin "--") (pinfunction "--_--") (pintype "bidirectional"))
    )
    (net (code "72") (name "unconnected-(BESCHL_PLAT1-Pad---)") (class "Default")
      (node (ref "BESCHL_PLAT1") (pin "---") (pinfunction "---_---") (pintype "bidirectional"))
    )
    (net (code "73") (name "unconnected-(BESCHL_PLAT1-Pad----)") (class "Default")
      (node (ref "BESCHL_PLAT1") (pin "----") (pinfunction "----_----") (pintype "bidirectional"))
    )
    (net (code "74") (name "unconnected-(BESCHL_PLAT1-Pad-----)") (class "Default")
      (node (ref "BESCHL_PLAT1") (pin "-----") (pinfunction "-----_-----") (pintype "bidirectional"))
    )
    (net (code "75") (name "unconnected-(BESCHL_PLAT1-PadINT2)") (class "Default")
      (node (ref "BESCHL_PLAT1") (pin "INT2") (pinfunction "INT2_INT2") (pintype "bidirectional"))
    )
    (net (code "76") (name "unconnected-(U$1-Pad-)") (class "Default")
      (node (ref "U$1") (pin "-") (pinfunction "-_-") (pintype "bidirectional"))
    )
    (net (code "77") (name "unconnected-(U$1-PadINT)") (class "Default")
      (node (ref "U$1") (pin "INT") (pinfunction "INT_INT") (pintype "bidirectional"))
    )
    (net (code "78") (name "unconnected-(U$2-PadD13)") (class "Default")
      (node (ref "U$2") (pin "D13") (pinfunction "D13_D13") (pintype "bidirectional"))
    )
    (net (code "79") (name "unconnected-(U$2-PadRESET)") (class "Default")
      (node (ref "U$2") (pin "RESET") (pinfunction "RESET_RESET") (pintype "bidirectional"))
    )
    (net (code "80") (name "unconnected-(U$2-PadRESET1)") (class "Default")
      (node (ref "U$2") (pin "RESET1") (pinfunction "RESET1_RESET1") (pintype "bidirectional"))
    )
    (net (code "81") (name "unconnected-(U$2-PadVIN)") (class "Default")
      (node (ref "U$2") (pin "VIN") (pinfunction "VIN_VIN") (pintype "bidirectional"))
    )
    (net (code "82") (name "unconnected-(U$3-Pad3)") (class "Default")
      (node (ref "U$3") (pin "3") (pinfunction "3_3") (pintype "bidirectional"))
    )
    (net (code "83") (name "unconnected-(U$3-Pad8)") (class "Default")
      (node (ref "U$3") (pin "8") (pinfunction "8_8") (pintype "bidirectional"))
    )
    (net (code "84") (name "unconnected-(U$8-PadSDO)") (class "Default")
      (node (ref "U$8") (pin "SDO") (pinfunction "SDO_SDO") (pintype "bidirectional"))
    )
  )
)
